# Power-V1_1.net
KiCad netlist of a schematic drawn in Altium Designer
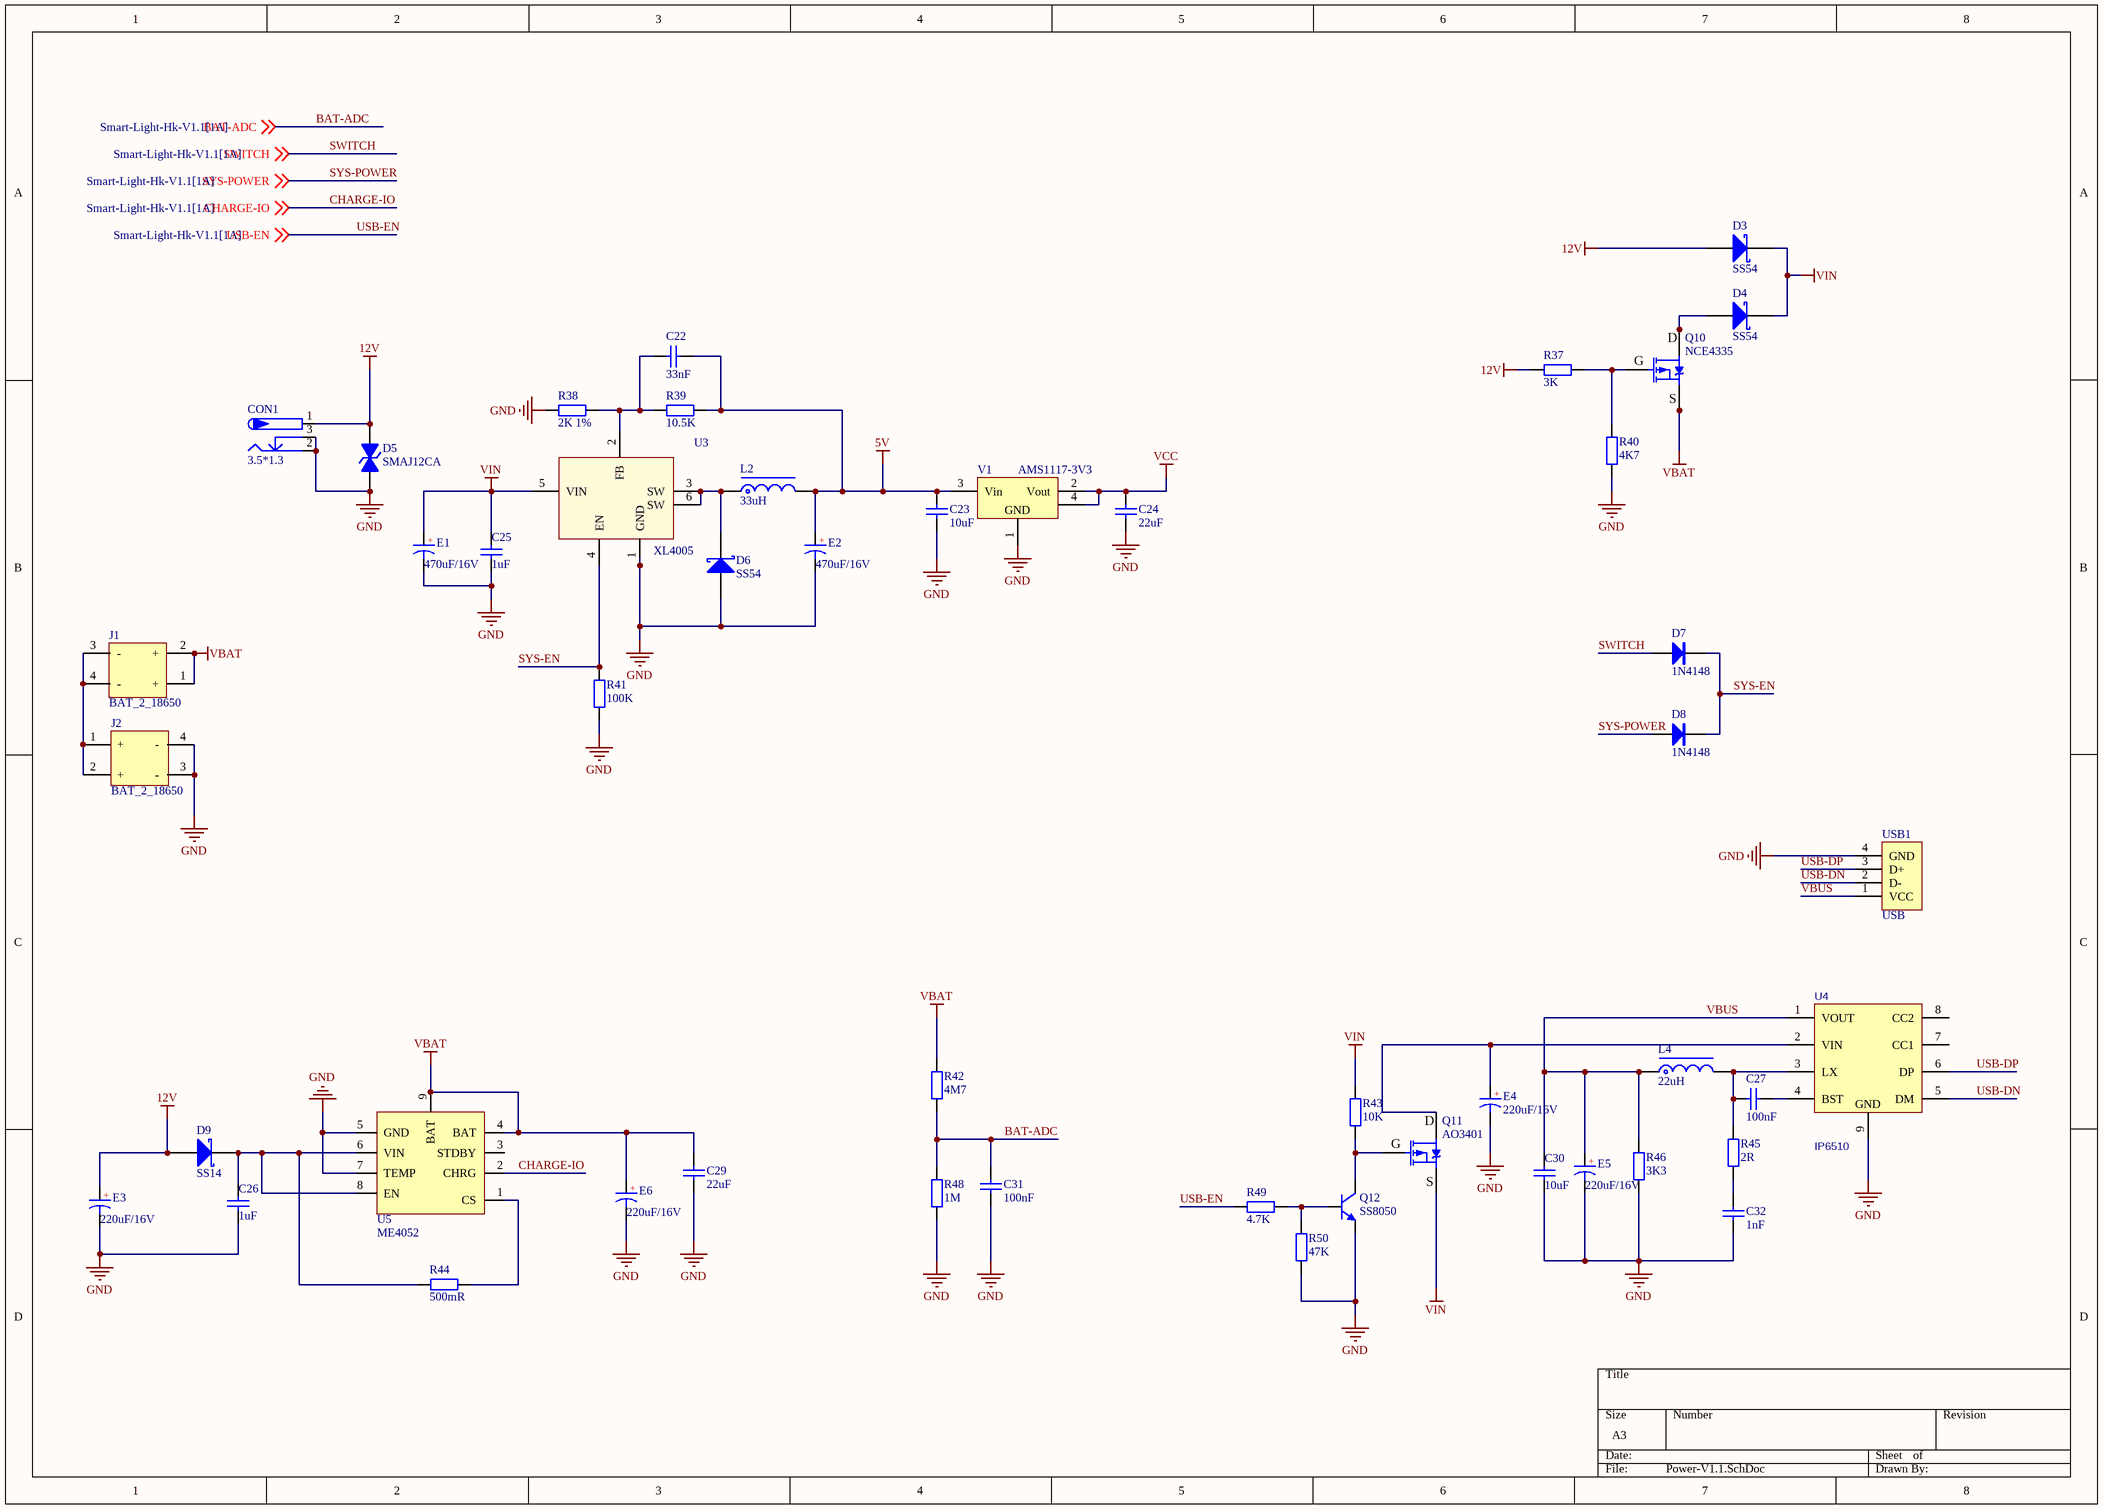
[diagram p0: Power-V1.1.SchDoc]

(export (version "E")
  (design (tool "Eeschema 10.0.6"))
  (components
    (comp (ref "C22")
      (value "33nF")
      (footprint "C0603_M")
      (description "贴片电容/MLCC电容")
      (libsource (lib "0.1 - 电阻-电容-电感-晶振-晶体-磁珠-电位器-法拉电容-馈通电容") (part "C"))
    )
    (comp (ref "C23")
      (value "10uF")
      (footprint "C0603_M")
      (description "贴片电容/MLCC电容")
      (libsource (lib "0.1 - 电阻-电容-电感-晶振-晶体-磁珠-电位器-法拉电容-馈通电容") (part "C"))
    )
    (comp (ref "C24")
      (value "22uF")
      (footprint "C1206_M")
      (description "贴片电容/MLCC电容")
      (libsource (lib "0.1 - 电阻-电容-电感-晶振-晶体-磁珠-电位器-法拉电容-馈通电容") (part "C"))
    )
    (comp (ref "C25")
      (value "1uF")
      (footprint "C0805_L")
      (description "贴片电容/MLCC电容")
      (libsource (lib "0.1 - 电阻-电容-电感-晶振-晶体-磁珠-电位器-法拉电容-馈通电容") (part "C"))
    )
    (comp (ref "C26")
      (value "1uF")
      (footprint "C0805_L")
      (description "贴片电容/MLCC电容")
      (libsource (lib "0.1 - 电阻-电容-电感-晶振-晶体-磁珠-电位器-法拉电容-馈通电容") (part "C"))
    )
    (comp (ref "C27")
      (value "100nF")
      (footprint "C0603_M")
      (description "贴片电容/MLCC电容")
      (libsource (lib "0.1 - 电阻-电容-电感-晶振-晶体-磁珠-电位器-法拉电容-馈通电容") (part "C"))
    )
    (comp (ref "C29")
      (value "22uF")
      (footprint "C1206_M")
      (description "贴片电容/MLCC电容")
      (libsource (lib "0.1 - 电阻-电容-电感-晶振-晶体-磁珠-电位器-法拉电容-馈通电容") (part "C"))
    )
    (comp (ref "C30")
      (value "10uF")
      (footprint "C1206_M")
      (description "贴片电容/MLCC电容")
      (libsource (lib "0.1 - 电阻-电容-电感-晶振-晶体-磁珠-电位器-法拉电容-馈通电容") (part "C"))
    )
    (comp (ref "C31")
      (value "100nF")
      (footprint "C0603_M")
      (description "贴片电容/MLCC电容")
      (libsource (lib "0.1 - 电阻-电容-电感-晶振-晶体-磁珠-电位器-法拉电容-馈通电容") (part "C"))
    )
    (comp (ref "C32")
      (value "1nF")
      (footprint "C0603_M")
      (description "贴片电容/MLCC电容")
      (libsource (lib "0.1 - 电阻-电容-电感-晶振-晶体-磁珠-电位器-法拉电容-馈通电容") (part "C"))
    )
    (comp (ref "CON1")
      (value "3.5*1.3")
      (footprint "DC-005")
      (description "低压电源接口")
      (libsource (lib "0.6 - 电源_音频_USB Type-C_HDMI_XT60_5557_D-SUB_RJ45_SD-TF_SIM插座") (part "DC002~DC005"))
    )
    (comp (ref "D3")
      (value "SS54")
      (footprint "SMA")
      (description "肖特基二极管")
      (libsource (lib "0.2 - 二极管-TVS-ESD-整流桥-放电管") (part "SS54"))
    )
    (comp (ref "D4")
      (value "SS54")
      (footprint "SMA")
      (description "肖特基二极管")
      (libsource (lib "0.2 - 二极管-TVS-ESD-整流桥-放电管") (part "SS54"))
    )
    (comp (ref "D5")
      (value "SMAJ12CA")
      (footprint "SMA")
      (description "双向TVS VRWM 12V")
      (libsource (lib "0.2 - 二极管-TVS-ESD-整流桥-放电管") (part "SMAJ12CA"))
    )
    (comp (ref "D6")
      (value "SS54")
      (footprint "SMA")
      (description "肖特基二极管")
      (libsource (lib "0.2 - 二极管-TVS-ESD-整流桥-放电管") (part "SS54"))
    )
    (comp (ref "D7")
      (value "1N4148")
      (footprint "SOD-123")
      (description "开关二极管")
      (libsource (lib "0.2 - 二极管-TVS-ESD-整流桥-放电管") (part "1N4148"))
    )
    (comp (ref "D8")
      (value "1N4148")
      (footprint "SOD-123")
      (description "开关二极管")
      (libsource (lib "0.2 - 二极管-TVS-ESD-整流桥-放电管") (part "1N4148"))
    )
    (comp (ref "D9")
      (value "SS14")
      (footprint "SMA")
      (description "肖特基二极管")
      (libsource (lib "0.2 - 二极管-TVS-ESD-整流桥-放电管") (part "SS14"))
    )
    (comp (ref "E1")
      (value "470uF/16V")
      (footprint "CE E(8*10.2)")
      (description "贴片电解电容")
      (libsource (lib "0.1 - 电阻-电容-电感-晶振-晶体-磁珠-电位器-法拉电容-馈通电容") (part "CE_SMD"))
    )
    (comp (ref "E2")
      (value "470uF/16V")
      (footprint "CE E(8*10.2)")
      (description "贴片电解电容")
      (libsource (lib "0.1 - 电阻-电容-电感-晶振-晶体-磁珠-电位器-法拉电容-馈通电容") (part "CE_SMD"))
    )
    (comp (ref "E3")
      (value "220uF/16V")
      (footprint "CE D(6.3*7.7)")
      (description "贴片电解电容")
      (libsource (lib "0.1 - 电阻-电容-电感-晶振-晶体-磁珠-电位器-法拉电容-馈通电容") (part "CE_SMD"))
    )
    (comp (ref "E4")
      (value "220uF/16V")
      (footprint "CE D(6.3*7.7)")
      (description "贴片电解电容")
      (libsource (lib "0.1 - 电阻-电容-电感-晶振-晶体-磁珠-电位器-法拉电容-馈通电容") (part "CE_SMD"))
    )
    (comp (ref "E5")
      (value "220uF/16V")
      (footprint "CE D(6.3*7.7)")
      (description "贴片电解电容")
      (libsource (lib "0.1 - 电阻-电容-电感-晶振-晶体-磁珠-电位器-法拉电容-馈通电容") (part "CE_SMD"))
    )
    (comp (ref "E6")
      (value "220uF/16V")
      (footprint "CE D(6.3*7.7)")
      (description "贴片电解电容")
      (libsource (lib "0.1 - 电阻-电容-电感-晶振-晶体-磁珠-电位器-法拉电容-馈通电容") (part "CE_SMD"))
    )
    (comp (ref "J1")
      (value "BAT_2_18650")
      (footprint "BAT_2_18650")
      (description "18650电池盒")
      (libsource (lib "0.6 - 电源_音频_USB Type-C_HDMI_XT60_5557_D-SUB_RJ45_SD-TF_SIM插座") (part "BAT_2_18650"))
    )
    (comp (ref "J2")
      (value "BAT_2_18650")
      (footprint "BAT_2_18650")
      (description "18650电池盒")
      (libsource (lib "") (part "BAT_2_18650_1"))
    )
    (comp (ref "L2")
      (value "33uH")
      (footprint "L-SMD-1265")
      (description "一体成型电感")
      (libsource (lib "0.1 - 电阻-电容-电感-晶振-晶体-磁珠-电位器-法拉电容-馈通电容") (part "L-Molding Choke"))
    )
    (comp (ref "L4")
      (value "22uH")
      (footprint "CDRH125")
      (description "CDRH功率屏蔽电感")
      (libsource (lib "0.1 - 电阻-电容-电感-晶振-晶体-磁珠-电位器-法拉电容-馈通电容") (part "L-CDRH"))
    )
    (comp (ref "Q10")
      (value "NCE4335")
      (footprint "SOP-8")
      (description "P沟道 -30V/-9A")
      (libsource (lib "0.4 - 三极管-场效应管-可控硅") (part "NCE4335"))
    )
    (comp (ref "Q11")
      (value "AO3401")
      (footprint "SOT23-3N")
      (description "P沟道 30V/4.2A")
      (libsource (lib "0.4 - 三极管-场效应管-可控硅") (part "AO3401"))
    )
    (comp (ref "Q12")
      (value "SS8050")
      (footprint "SOT23-3N")
      (description "高频放大-NPN型")
      (libsource (lib "0.4 - 三极管-场效应管-可控硅") (part "8050-SMD"))
    )
    (comp (ref "R37")
      (value "3K")
      (footprint "R0603_M")
      (description "贴片电阻")
      (libsource (lib "0.1 - 电阻-电容-电感-晶振-晶体-磁珠-电位器-法拉电容-馈通电容") (part "R"))
    )
    (comp (ref "R38")
      (value "2K 1%")
      (footprint "R0603_M")
      (description "贴片电阻")
      (libsource (lib "0.1 - 电阻-电容-电感-晶振-晶体-磁珠-电位器-法拉电容-馈通电容") (part "R"))
    )
    (comp (ref "R39")
      (value "10.5K")
      (footprint "R0603_M")
      (description "贴片电阻")
      (libsource (lib "0.1 - 电阻-电容-电感-晶振-晶体-磁珠-电位器-法拉电容-馈通电容") (part "R"))
    )
    (comp (ref "R40")
      (value "4K7")
      (footprint "R0603_M")
      (description "贴片电阻")
      (libsource (lib "0.1 - 电阻-电容-电感-晶振-晶体-磁珠-电位器-法拉电容-馈通电容") (part "R"))
    )
    (comp (ref "R41")
      (value "100K")
      (footprint "R0603_M")
      (description "贴片电阻")
      (libsource (lib "0.1 - 电阻-电容-电感-晶振-晶体-磁珠-电位器-法拉电容-馈通电容") (part "R"))
    )
    (comp (ref "R42")
      (value "4M7")
      (footprint "R0603_M")
      (description "贴片电阻")
      (libsource (lib "0.1 - 电阻-电容-电感-晶振-晶体-磁珠-电位器-法拉电容-馈通电容") (part "R"))
    )
    (comp (ref "R43")
      (value "10K")
      (footprint "R0603_M")
      (description "贴片电阻")
      (libsource (lib "0.1 - 电阻-电容-电感-晶振-晶体-磁珠-电位器-法拉电容-馈通电容") (part "R"))
    )
    (comp (ref "R44")
      (value "500mR")
      (footprint "R1206_L")
      (description "贴片电阻")
      (libsource (lib "0.1 - 电阻-电容-电感-晶振-晶体-磁珠-电位器-法拉电容-馈通电容") (part "R"))
    )
    (comp (ref "R45")
      (value "2R")
      (footprint "R0603_M")
      (description "贴片电阻")
      (libsource (lib "0.1 - 电阻-电容-电感-晶振-晶体-磁珠-电位器-法拉电容-馈通电容") (part "R"))
    )
    (comp (ref "R46")
      (value "3K3")
      (footprint "R0603_M")
      (description "贴片电阻")
      (libsource (lib "0.1 - 电阻-电容-电感-晶振-晶体-磁珠-电位器-法拉电容-馈通电容") (part "R"))
    )
    (comp (ref "R48")
      (value "1M")
      (footprint "R0603_M")
      (description "贴片电阻")
      (libsource (lib "0.1 - 电阻-电容-电感-晶振-晶体-磁珠-电位器-法拉电容-馈通电容") (part "R"))
    )
    (comp (ref "R49")
      (value "4.7K")
      (footprint "R0603_M")
      (description "贴片电阻")
      (libsource (lib "0.1 - 电阻-电容-电感-晶振-晶体-磁珠-电位器-法拉电容-馈通电容") (part "R"))
    )
    (comp (ref "R50")
      (value "47K")
      (footprint "R0603_M")
      (description "贴片电阻")
      (libsource (lib "0.1 - 电阻-电容-电感-晶振-晶体-磁珠-电位器-法拉电容-馈通电容") (part "R"))
    )
    (comp (ref "U3")
      (value "XL4005")
      (footprint "TO263-5A")
      (description "降压芯片5A   xl4003 4A")
      (libsource (lib "0.7 - 电源类芯片") (part "XL4005"))
    )
    (comp (ref "U4")
      (value "IP6510")
      (footprint "ESOP8_M")
      (description "快充芯片")
      (libsource (lib "0.7 - 电源类芯片") (part "IP6510"))
    )
    (comp (ref "U5")
      (value "ME4052")
      (footprint "ESOP8_M")
      (description "两节锂电池充电芯片")
      (libsource (lib "0.7 - 电源类芯片") (part "ME4052"))
    )
    (comp (ref "USB1")
      (value "USB")
      (footprint "USB2.0_Type-A_SMD_F_2")
      (description "USB2.0_Type-A母座")
      (libsource (lib "0.6 - 电源_音频_USB Type-C_HDMI_XT60_5557_D-SUB_RJ45_SD-TF_SIM插座") (part "USB2.0_Type-A_F"))
    )
    (comp (ref "V1")
      (value "AMS1117-3V3")
      (footprint "SOT223_L")
      (description "三端稳压芯片")
      (libsource (lib "0.7 - 电源类芯片") (part "AMS1117"))
    )
  )
  (nets
    (net (code "2") (name "/SYS-EN") (class "Default")
      (node (ref "D7") (pin "2") (pinfunction "K_2") (pintype "passive"))
      (node (ref "D8") (pin "2") (pinfunction "K_2") (pintype "passive"))
      (node (ref "R41") (pin "2") (pinfunction "2_2") (pintype "passive"))
      (node (ref "U3") (pin "4") (pinfunction "EN_4") (pintype "passive"))
    )
    (net (code "3") (name "/USB-DN") (class "Default")
      (node (ref "U4") (pin "5") (pinfunction "DM_5") (pintype "passive"))
      (node (ref "USB1") (pin "2") (pinfunction "D-_2") (pintype "passive"))
    )
    (net (code "4") (name "/USB-DP") (class "Default")
      (node (ref "U4") (pin "6") (pinfunction "DP_6") (pintype "passive"))
      (node (ref "USB1") (pin "3") (pinfunction "D+_3") (pintype "passive"))
    )
    (net (code "5") (name "/VBUS") (class "Default")
      (node (ref "C30") (pin "2") (pinfunction "2_2") (pintype "passive"))
      (node (ref "E5") (pin "1") (pinfunction "1_1") (pintype "passive"))
      (node (ref "L4") (pin "1") (pinfunction "1_1") (pintype "passive"))
      (node (ref "R46") (pin "1") (pinfunction "1_1") (pintype "passive"))
      (node (ref "U4") (pin "1") (pinfunction "VOUT_1") (pintype "passive"))
      (node (ref "USB1") (pin "1") (pinfunction "VCC_1") (pintype "passive"))
    )
    (net (code "6") (name "5V") (class "Default")
      (node (ref "C22") (pin "2") (pinfunction "2_2") (pintype "passive"))
      (node (ref "C23") (pin "2") (pinfunction "2_2") (pintype "passive"))
      (node (ref "E2") (pin "1") (pinfunction "1_1") (pintype "passive"))
      (node (ref "L2") (pin "2") (pinfunction "2_2") (pintype "passive"))
      (node (ref "R39") (pin "2") (pinfunction "2_2") (pintype "passive"))
      (node (ref "V1") (pin "3") (pinfunction "Vin_3") (pintype "passive"))
    )
    (net (code "7") (name "12V") (class "Default")
      (node (ref "CON1") (pin "1") (pintype "power_in"))
      (node (ref "D3") (pin "1") (pinfunction "A_1") (pintype "passive"))
      (node (ref "D5") (pin "2") (pinfunction "K_2") (pintype "passive"))
      (node (ref "D9") (pin "1") (pinfunction "A_1") (pintype "passive"))
      (node (ref "E3") (pin "1") (pinfunction "1_1") (pintype "passive"))
      (node (ref "R37") (pin "2") (pinfunction "2_2") (pintype "passive"))
    )
    (net (code "8") (name "BAT-ADC") (class "Default")
      (node (ref "C31") (pin "2") (pinfunction "2_2") (pintype "passive"))
      (node (ref "R42") (pin "1") (pinfunction "1_1") (pintype "passive"))
      (node (ref "R48") (pin "2") (pinfunction "2_2") (pintype "passive"))
    )
    (net (code "9") (name "CHARGE-IO") (class "Default")
      (node (ref "U5") (pin "2") (pinfunction "CHRG_2") (pintype "passive"))
    )
    (net (code "10") (name "GND") (class "Default")
      (node (ref "C23") (pin "1") (pinfunction "1_1") (pintype "passive"))
      (node (ref "C24") (pin "1") (pinfunction "1_1") (pintype "passive"))
      (node (ref "C25") (pin "1") (pinfunction "1_1") (pintype "passive"))
      (node (ref "C26") (pin "1") (pinfunction "1_1") (pintype "passive"))
      (node (ref "C29") (pin "1") (pinfunction "1_1") (pintype "passive"))
      (node (ref "C30") (pin "1") (pinfunction "1_1") (pintype "passive"))
      (node (ref "C31") (pin "1") (pinfunction "1_1") (pintype "passive"))
      (node (ref "C32") (pin "2") (pinfunction "2_2") (pintype "passive"))
      (node (ref "CON1") (pin "2") (pintype "power_in"))
      (node (ref "CON1") (pin "3") (pintype "power_in"))
      (node (ref "D5") (pin "1") (pinfunction "A_1") (pintype "passive"))
      (node (ref "D6") (pin "1") (pinfunction "A_1") (pintype "passive"))
      (node (ref "E1") (pin "2") (pinfunction "2_2") (pintype "passive"))
      (node (ref "E2") (pin "2") (pinfunction "2_2") (pintype "passive"))
      (node (ref "E3") (pin "2") (pinfunction "2_2") (pintype "passive"))
      (node (ref "E4") (pin "2") (pinfunction "2_2") (pintype "passive"))
      (node (ref "E5") (pin "2") (pinfunction "2_2") (pintype "passive"))
      (node (ref "E6") (pin "2") (pinfunction "2_2") (pintype "passive"))
      (node (ref "J2") (pin "3") (pinfunction "-_3") (pintype "passive"))
      (node (ref "J2") (pin "4") (pinfunction "-_4") (pintype "passive"))
      (node (ref "Q12") (pin "2") (pinfunction "E_2") (pintype "passive"))
      (node (ref "R38") (pin "1") (pinfunction "1_1") (pintype "passive"))
      (node (ref "R40") (pin "1") (pinfunction "1_1") (pintype "passive"))
      (node (ref "R41") (pin "1") (pinfunction "1_1") (pintype "passive"))
      (node (ref "R46") (pin "2") (pinfunction "2_2") (pintype "passive"))
      (node (ref "R48") (pin "1") (pinfunction "1_1") (pintype "passive"))
      (node (ref "R50") (pin "2") (pinfunction "2_2") (pintype "passive"))
      (node (ref "U3") (pin "1") (pinfunction "GND_1") (pintype "passive"))
      (node (ref "U4") (pin "9") (pinfunction "GND_9") (pintype "passive"))
      (node (ref "U5") (pin "5") (pinfunction "GND_5") (pintype "passive"))
      (node (ref "U5") (pin "7") (pinfunction "TEMP_7") (pintype "passive"))
      (node (ref "USB1") (pin "4") (pinfunction "GND_4") (pintype "passive"))
      (node (ref "V1") (pin "1") (pinfunction "GND_1") (pintype "passive"))
    )
    (net (code "11") (name "Net-(C32-Pad1)") (class "Default")
      (node (ref "C32") (pin "1") (pinfunction "1_1") (pintype "passive"))
      (node (ref "R45") (pin "1") (pinfunction "1_1") (pintype "passive"))
    )
    (net (code "12") (name "Net-(D4-A)") (class "Default")
      (node (ref "D4") (pin "1") (pinfunction "A_1") (pintype "passive"))
      (node (ref "Q10") (pin "5") (pinfunction "D_5") (pintype "passive"))
      (node (ref "Q10") (pin "6") (pinfunction "D_6") (pintype "tri_state"))
      (node (ref "Q10") (pin "7") (pinfunction "D_7") (pintype "passive"))
      (node (ref "Q10") (pin "8") (pinfunction "D_8") (pintype "passive"))
    )
    (net (code "13") (name "Net-(D6-K)") (class "Default")
      (node (ref "D6") (pin "2") (pinfunction "K_2") (pintype "passive"))
      (node (ref "L2") (pin "1") (pinfunction "1_1") (pintype "passive"))
      (node (ref "U3") (pin "3") (pinfunction "SW_3") (pintype "passive"))
      (node (ref "U3") (pin "6") (pinfunction "SW_6") (pintype "passive"))
    )
    (net (code "14") (name "Net-(D9-K)") (class "Default")
      (node (ref "C26") (pin "2") (pinfunction "2_2") (pintype "passive"))
      (node (ref "D9") (pin "2") (pinfunction "K_2") (pintype "passive"))
      (node (ref "R44") (pin "1") (pinfunction "1_1") (pintype "passive"))
      (node (ref "U5") (pin "6") (pinfunction "VIN_6") (pintype "passive"))
      (node (ref "U5") (pin "8") (pinfunction "EN_8") (pintype "passive"))
    )
    (net (code "15") (name "Net-(J1---Pad3)") (class "Default")
      (node (ref "J1") (pin "3") (pinfunction "-_3") (pintype "passive"))
      (node (ref "J1") (pin "4") (pinfunction "-_4") (pintype "passive"))
      (node (ref "J2") (pin "1") (pinfunction "+_1") (pintype "passive"))
      (node (ref "J2") (pin "2") (pinfunction "+_2") (pintype "passive"))
    )
    (net (code "16") (name "Net-(Q10-G)") (class "Default")
      (node (ref "Q10") (pin "4") (pinfunction "G_4") (pintype "passive"))
      (node (ref "R37") (pin "1") (pinfunction "1_1") (pintype "passive"))
      (node (ref "R40") (pin "2") (pinfunction "2_2") (pintype "passive"))
    )
    (net (code "17") (name "Net-(Q11-D)") (class "Default")
      (node (ref "E4") (pin "1") (pinfunction "1_1") (pintype "passive"))
      (node (ref "Q11") (pin "3") (pinfunction "D_3") (pintype "passive"))
      (node (ref "U4") (pin "2") (pinfunction "VIN_2") (pintype "passive"))
    )
    (net (code "18") (name "Net-(Q11-G)") (class "Default")
      (node (ref "Q11") (pin "1") (pinfunction "G_1") (pintype "passive"))
      (node (ref "Q12") (pin "3") (pinfunction "C_3") (pintype "passive"))
      (node (ref "R43") (pin "1") (pinfunction "1_1") (pintype "passive"))
    )
    (net (code "19") (name "Net-(Q12-B)") (class "Default")
      (node (ref "Q12") (pin "1") (pinfunction "B_1") (pintype "passive"))
      (node (ref "R49") (pin "1") (pinfunction "1_1") (pintype "passive"))
      (node (ref "R50") (pin "1") (pinfunction "1_1") (pintype "passive"))
    )
    (net (code "20") (name "Net-(U3-FB)") (class "Default")
      (node (ref "C22") (pin "1") (pinfunction "1_1") (pintype "passive"))
      (node (ref "R38") (pin "2") (pinfunction "2_2") (pintype "passive"))
      (node (ref "R39") (pin "1") (pinfunction "1_1") (pintype "passive"))
      (node (ref "U3") (pin "2") (pinfunction "FB_2") (pintype "passive"))
    )
    (net (code "21") (name "Net-(U4-BST)") (class "Default")
      (node (ref "C27") (pin "1") (pinfunction "1_1") (pintype "passive"))
      (node (ref "U4") (pin "4") (pinfunction "BST_4") (pintype "passive"))
    )
    (net (code "22") (name "Net-(U4-LX)") (class "Default")
      (node (ref "C27") (pin "2") (pinfunction "2_2") (pintype "passive"))
      (node (ref "L4") (pin "2") (pinfunction "2_2") (pintype "passive"))
      (node (ref "R45") (pin "2") (pinfunction "2_2") (pintype "passive"))
      (node (ref "U4") (pin "3") (pinfunction "LX_3") (pintype "passive"))
    )
    (net (code "23") (name "Net-(U5-CS)") (class "Default")
      (node (ref "R44") (pin "2") (pinfunction "2_2") (pintype "passive"))
      (node (ref "U5") (pin "1") (pinfunction "CS_1") (pintype "passive"))
    )
    (net (code "24") (name "SWITCH") (class "Default")
      (node (ref "D7") (pin "1") (pinfunction "A_1") (pintype "passive"))
    )
    (net (code "25") (name "SYS-POWER") (class "Default")
      (node (ref "D8") (pin "1") (pinfunction "A_1") (pintype "passive"))
    )
    (net (code "26") (name "USB-EN") (class "Default")
      (node (ref "R49") (pin "2") (pinfunction "2_2") (pintype "passive"))
    )
    (net (code "27") (name "VBAT") (class "Default")
      (node (ref "C29") (pin "2") (pinfunction "2_2") (pintype "passive"))
      (node (ref "E6") (pin "1") (pinfunction "1_1") (pintype "passive"))
      (node (ref "J1") (pin "1") (pinfunction "+_1") (pintype "passive"))
      (node (ref "J1") (pin "2") (pinfunction "+_2") (pintype "passive"))
      (node (ref "Q10") (pin "1") (pinfunction "S_1") (pintype "passive"))
      (node (ref "Q10") (pin "2") (pinfunction "S_2") (pintype "passive"))
      (node (ref "Q10") (pin "3") (pinfunction "S_3") (pintype "passive"))
      (node (ref "R42") (pin "2") (pinfunction "2_2") (pintype "passive"))
      (node (ref "U5") (pin "4") (pinfunction "BAT_4") (pintype "passive"))
      (node (ref "U5") (pin "9") (pinfunction "BAT_9") (pintype "passive"))
    )
    (net (code "28") (name "VCC") (class "Default")
      (node (ref "C24") (pin "2") (pinfunction "2_2") (pintype "passive"))
      (node (ref "V1") (pin "2") (pinfunction "Vout_2") (pintype "passive"))
      (node (ref "V1") (pin "4") (pinfunction "GND_4") (pintype "passive"))
    )
    (net (code "29") (name "VIN") (class "Default")
      (node (ref "C25") (pin "2") (pinfunction "2_2") (pintype "passive"))
      (node (ref "D3") (pin "2") (pinfunction "K_2") (pintype "passive"))
      (node (ref "D4") (pin "2") (pinfunction "K_2") (pintype "passive"))
      (node (ref "E1") (pin "1") (pinfunction "1_1") (pintype "passive"))
      (node (ref "Q11") (pin "2") (pinfunction "S_2") (pintype "passive"))
      (node (ref "R43") (pin "2") (pinfunction "2_2") (pintype "passive"))
      (node (ref "U3") (pin "5") (pinfunction "VIN_5") (pintype "passive"))
    )
    (net (code "30") (name "unconnected-(U4-CC1-Pad7)") (class "Default")
      (node (ref "U4") (pin "7") (pinfunction "CC1_7") (pintype "passive"))
    )
    (net (code "31") (name "unconnected-(U4-CC2-Pad8)") (class "Default")
      (node (ref "U4") (pin "8") (pinfunction "CC2_8") (pintype "passive"))
    )
    (net (code "32") (name "unconnected-(U5-STDBY-Pad3)") (class "Default")
      (node (ref "U5") (pin "3") (pinfunction "STDBY_3") (pintype "passive"))
    )
  )
)
